# mainboard.net
KiCad netlist of a schematic drawn in EAGLE
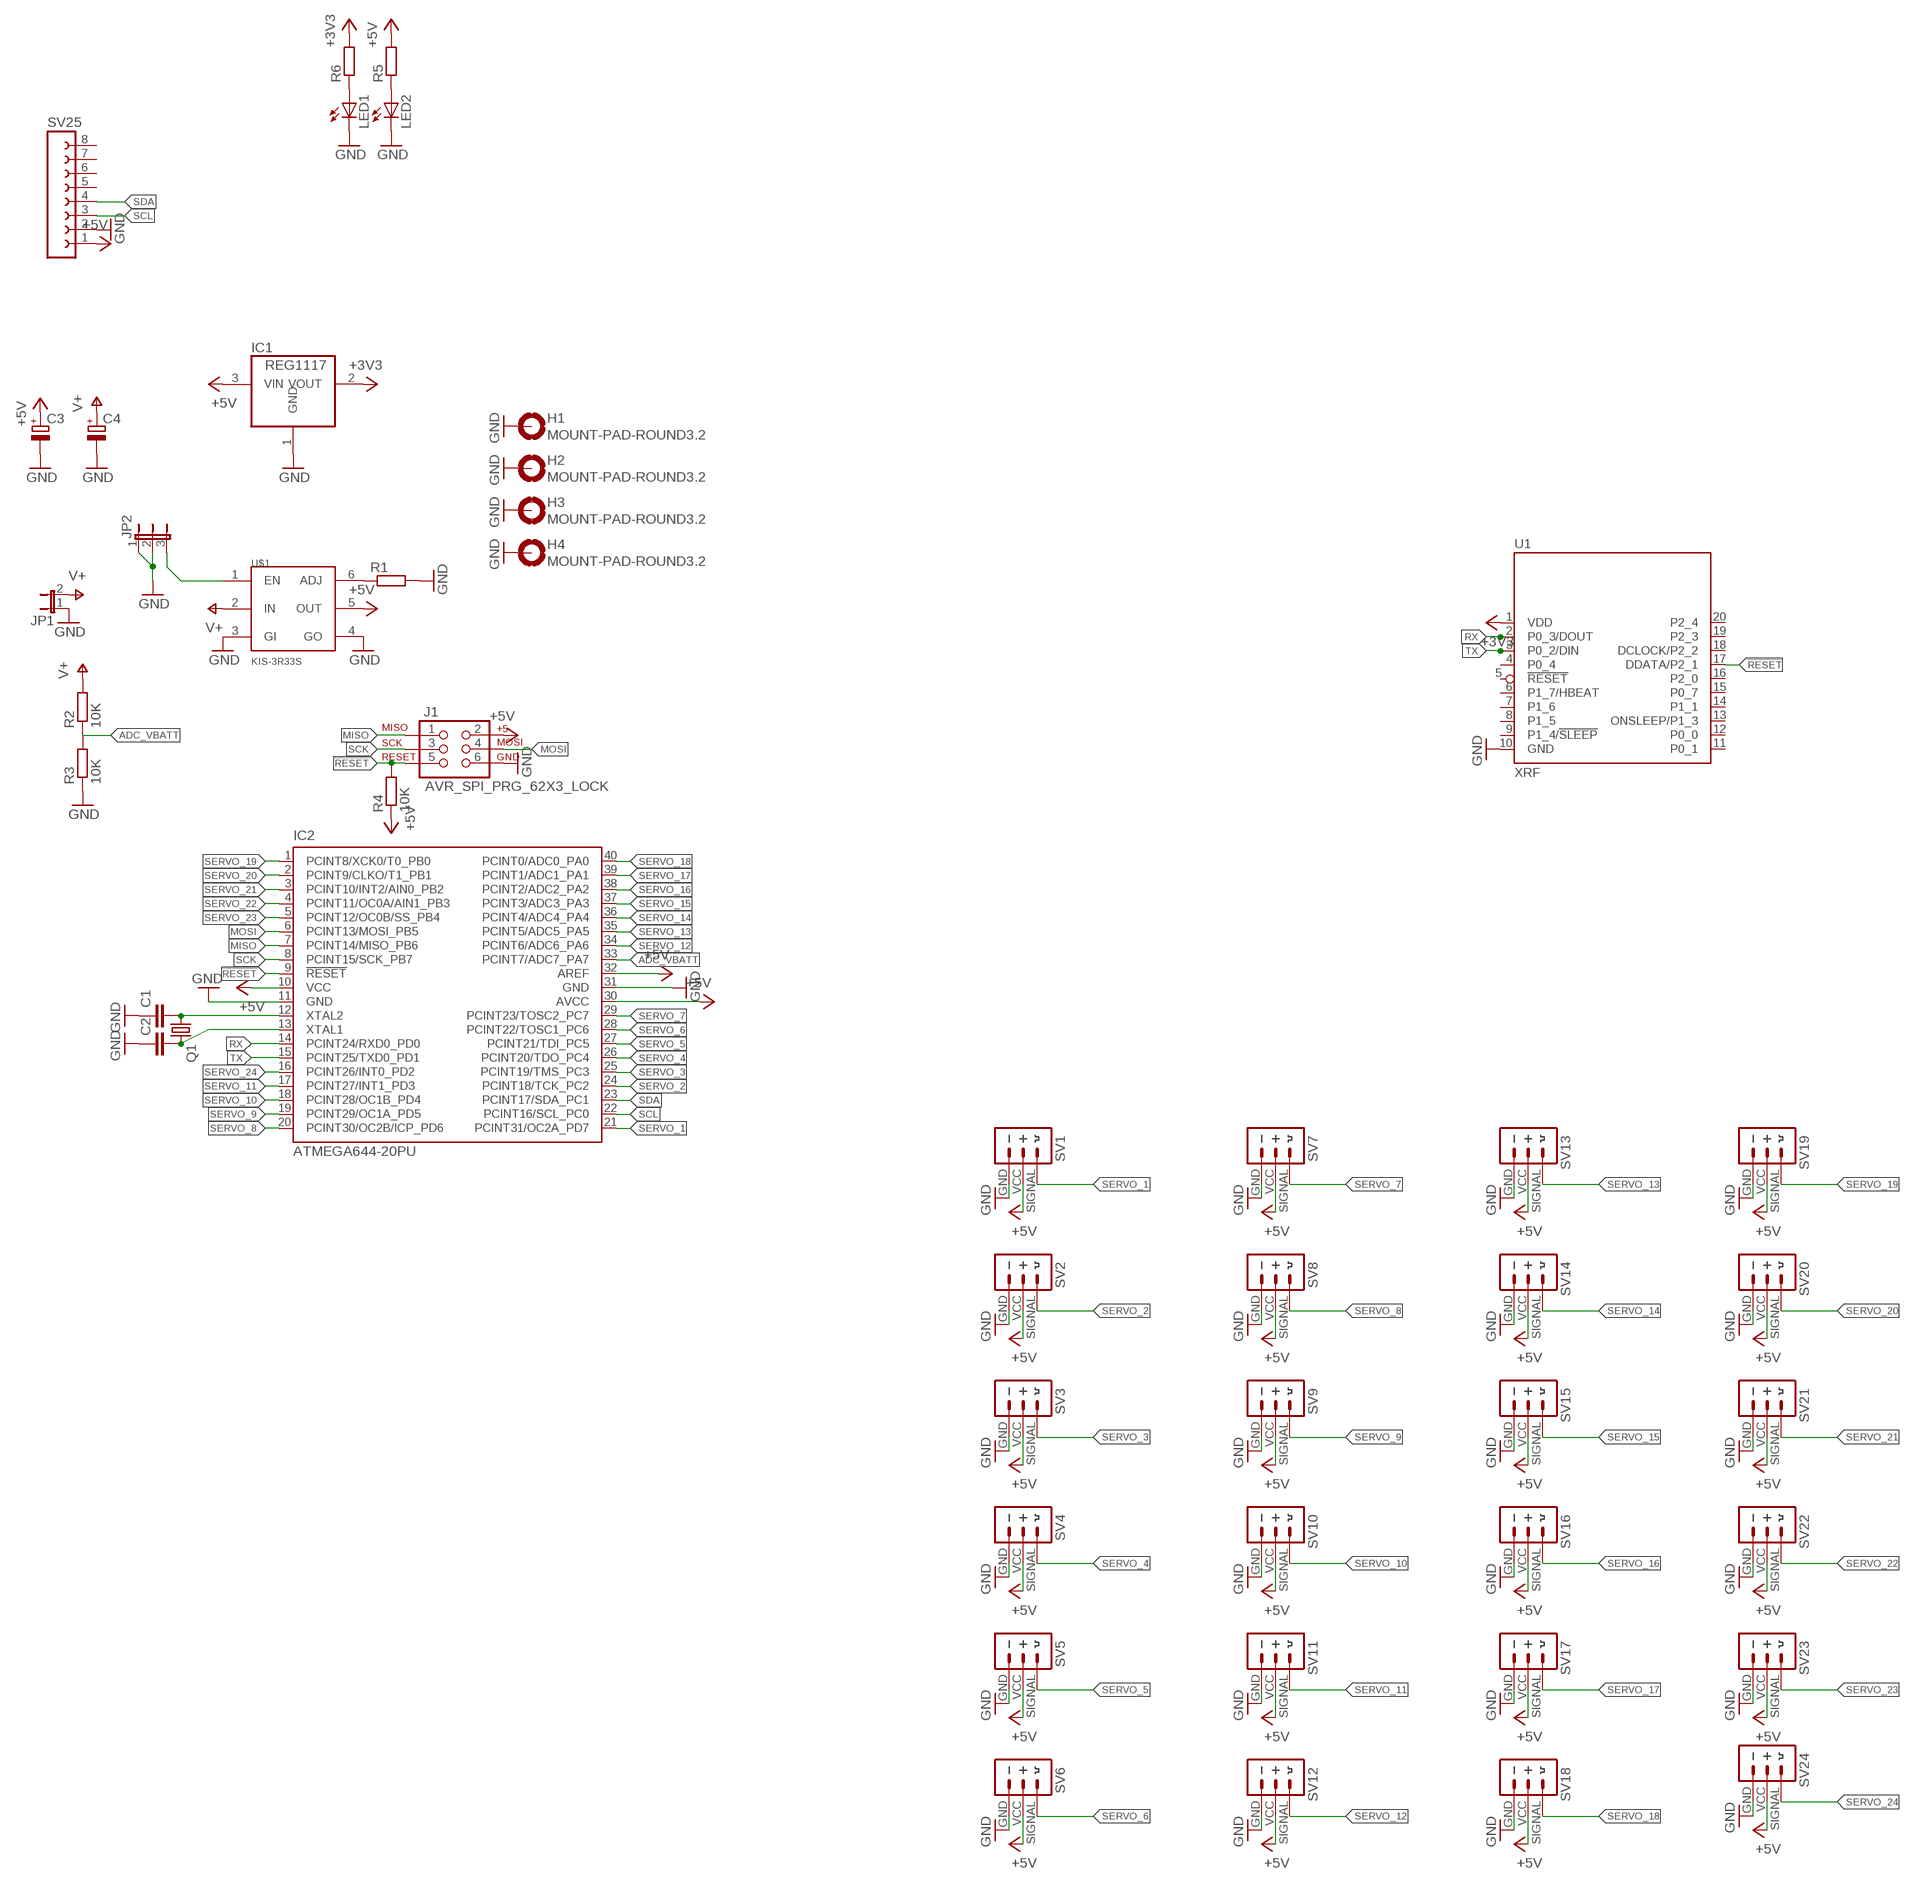
[diagram p0: schematic, sheet 1]

(export (version "E")
  (design (tool "Eeschema 10.0.6"))
  (components
    (comp (ref "C1")
      (value "C-EU025-025X050")
      (footprint "eagle-import:C025-025X050")
      (libsource (lib "eagle-import") (part "C-EU025-025X050"))
    )
    (comp (ref "C2")
      (value "C-EU025-025X050")
      (footprint "eagle-import:C025-025X050")
      (libsource (lib "eagle-import") (part "C-EU025-025X050"))
    )
    (comp (ref "C3")
      (value "CPOL-EUE2.5-7")
      (footprint "eagle-import:E2,5-7")
      (libsource (lib "eagle-import") (part "CPOL-EUE2.5-7"))
    )
    (comp (ref "C4")
      (value "CPOL-EUE2.5-7")
      (footprint "eagle-import:E2,5-7")
      (libsource (lib "eagle-import") (part "CPOL-EUE2.5-7"))
    )
    (comp (ref "H1")
      (value "MOUNT-PAD-ROUND3.2")
      (footprint "eagle-import:3,2-PAD")
      (libsource (lib "eagle-import") (part "MOUNT-PAD-ROUND3.2"))
    )
    (comp (ref "H2")
      (value "MOUNT-PAD-ROUND3.2")
      (footprint "eagle-import:3,2-PAD")
      (libsource (lib "eagle-import") (part "MOUNT-PAD-ROUND3.2"))
    )
    (comp (ref "H3")
      (value "MOUNT-PAD-ROUND3.2")
      (footprint "eagle-import:3,2-PAD")
      (libsource (lib "eagle-import") (part "MOUNT-PAD-ROUND3.2"))
    )
    (comp (ref "H4")
      (value "MOUNT-PAD-ROUND3.2")
      (footprint "eagle-import:3,2-PAD")
      (libsource (lib "eagle-import") (part "MOUNT-PAD-ROUND3.2"))
    )
    (comp (ref "IC1")
      (value "REG1117")
      (footprint "eagle-import:SOT223")
      (libsource (lib "eagle-import") (part "REG1117"))
    )
    (comp (ref "IC2")
      (value "ATMEGA644-20PU")
      (footprint "eagle-import:DIL40")
      (libsource (lib "eagle-import") (part "ATMEGA644-PU20"))
    )
    (comp (ref "J1")
      (value "AVR_SPI_PRG_62X3_LOCK")
      (footprint "eagle-import:2X3_LOCK")
      (libsource (lib "eagle-import") (part "AVR_SPI_PRG_62X3_LOCK"))
    )
    (comp (ref "JP1")
      (value "JP1E")
      (footprint "eagle-import:JP1")
      (libsource (lib "eagle-import") (part "JP1E"))
    )
    (comp (ref "JP2")
      (value "JP2E")
      (footprint "eagle-import:JP2")
      (libsource (lib "eagle-import") (part "JP2E"))
    )
    (comp (ref "LED1")
      (value "LED5MM")
      (footprint "eagle-import:LED5MM")
      (libsource (lib "eagle-import") (part "LED5MM"))
    )
    (comp (ref "LED2")
      (value "LED5MM")
      (footprint "eagle-import:LED5MM")
      (libsource (lib "eagle-import") (part "LED5MM"))
    )
    (comp (ref "Q1")
      (value "CRYSTALHC49U-V")
      (footprint "eagle-import:HC49U-V")
      (libsource (lib "eagle-import") (part "CRYSTALHC49U-V"))
    )
    (comp (ref "R1")
      (value "R-EU_0207/10")
      (footprint "eagle-import:0207_10")
      (libsource (lib "eagle-import") (part "R-EU_0207/10"))
    )
    (comp (ref "R2")
      (value "10K")
      (footprint "eagle-import:0204_5")
      (libsource (lib "eagle-import") (part "R-EU_0204/5"))
    )
    (comp (ref "R3")
      (value "10K")
      (footprint "eagle-import:0204_5")
      (libsource (lib "eagle-import") (part "R-EU_0204/5"))
    )
    (comp (ref "R4")
      (value "10K")
      (footprint "eagle-import:0204V")
      (libsource (lib "eagle-import") (part "R-EU_0204/2V"))
    )
    (comp (ref "R5")
      (value "R-EU_0204/2V")
      (footprint "eagle-import:0204V")
      (libsource (lib "eagle-import") (part "R-EU_0204/2V"))
    )
    (comp (ref "R6")
      (value "R-EU_0204/2V")
      (footprint "eagle-import:0204V")
      (libsource (lib "eagle-import") (part "R-EU_0204/2V"))
    )
    (comp (ref "SV1")
      (value "SERVO")
      (footprint "eagle-import:SERVO")
      (libsource (lib "eagle-import") (part "SERVO"))
    )
    (comp (ref "SV2")
      (value "SERVO")
      (footprint "eagle-import:SERVO")
      (libsource (lib "eagle-import") (part "SERVO"))
    )
    (comp (ref "SV3")
      (value "SERVO")
      (footprint "eagle-import:SERVO")
      (libsource (lib "eagle-import") (part "SERVO"))
    )
    (comp (ref "SV4")
      (value "SERVO")
      (footprint "eagle-import:SERVO")
      (libsource (lib "eagle-import") (part "SERVO"))
    )
    (comp (ref "SV5")
      (value "SERVO")
      (footprint "eagle-import:SERVO")
      (libsource (lib "eagle-import") (part "SERVO"))
    )
    (comp (ref "SV6")
      (value "SERVO")
      (footprint "eagle-import:SERVO")
      (libsource (lib "eagle-import") (part "SERVO"))
    )
    (comp (ref "SV7")
      (value "SERVO")
      (footprint "eagle-import:SERVO")
      (libsource (lib "eagle-import") (part "SERVO"))
    )
    (comp (ref "SV8")
      (value "SERVO")
      (footprint "eagle-import:SERVO")
      (libsource (lib "eagle-import") (part "SERVO"))
    )
    (comp (ref "SV9")
      (value "SERVO")
      (footprint "eagle-import:SERVO")
      (libsource (lib "eagle-import") (part "SERVO"))
    )
    (comp (ref "SV10")
      (value "SERVO")
      (footprint "eagle-import:SERVO")
      (libsource (lib "eagle-import") (part "SERVO"))
    )
    (comp (ref "SV11")
      (value "SERVO")
      (footprint "eagle-import:SERVO")
      (libsource (lib "eagle-import") (part "SERVO"))
    )
    (comp (ref "SV12")
      (value "SERVO")
      (footprint "eagle-import:SERVO")
      (libsource (lib "eagle-import") (part "SERVO"))
    )
    (comp (ref "SV13")
      (value "SERVO")
      (footprint "eagle-import:SERVO")
      (libsource (lib "eagle-import") (part "SERVO"))
    )
    (comp (ref "SV14")
      (value "SERVO")
      (footprint "eagle-import:SERVO")
      (libsource (lib "eagle-import") (part "SERVO"))
    )
    (comp (ref "SV15")
      (value "SERVO")
      (footprint "eagle-import:SERVO")
      (libsource (lib "eagle-import") (part "SERVO"))
    )
    (comp (ref "SV16")
      (value "SERVO")
      (footprint "eagle-import:SERVO")
      (libsource (lib "eagle-import") (part "SERVO"))
    )
    (comp (ref "SV17")
      (value "SERVO")
      (footprint "eagle-import:SERVO")
      (libsource (lib "eagle-import") (part "SERVO"))
    )
    (comp (ref "SV18")
      (value "SERVO")
      (footprint "eagle-import:SERVO")
      (libsource (lib "eagle-import") (part "SERVO"))
    )
    (comp (ref "SV19")
      (value "SERVO")
      (footprint "eagle-import:SERVO")
      (libsource (lib "eagle-import") (part "SERVO"))
    )
    (comp (ref "SV20")
      (value "SERVO")
      (footprint "eagle-import:SERVO")
      (libsource (lib "eagle-import") (part "SERVO"))
    )
    (comp (ref "SV21")
      (value "SERVO")
      (footprint "eagle-import:SERVO")
      (libsource (lib "eagle-import") (part "SERVO"))
    )
    (comp (ref "SV22")
      (value "SERVO")
      (footprint "eagle-import:SERVO")
      (libsource (lib "eagle-import") (part "SERVO"))
    )
    (comp (ref "SV23")
      (value "SERVO")
      (footprint "eagle-import:SERVO")
      (libsource (lib "eagle-import") (part "SERVO"))
    )
    (comp (ref "SV24")
      (value "SERVO")
      (footprint "eagle-import:SERVO")
      (libsource (lib "eagle-import") (part "SERVO"))
    )
    (comp (ref "SV25")
      (value "FE08-1")
      (footprint "eagle-import:FE08")
      (libsource (lib "eagle-import") (part "FE08-1"))
    )
    (comp (ref "U$1")
      (value "KIS-3R33S")
      (footprint "eagle-import:KIS-3R33S")
      (libsource (lib "eagle-import") (part "KIS-3R33S"))
    )
    (comp (ref "U1")
      (value "XRF")
      (footprint "eagle-import:XRF")
      (libsource (lib "eagle-import") (part "XRF"))
    )
  )
  (nets
    (net (code "1") (name "+3V3") (class "Default")
      (node (ref "IC1") (pin "2") (pinfunction "VOUT_2") (pintype "output"))
      (node (ref "R6") (pin "2") (pinfunction "2_2") (pintype "passive"))
      (node (ref "U1") (pin "1") (pinfunction "VDD_1") (pintype "power_in"))
    )
    (net (code "2") (name "+5V") (class "Default")
      (node (ref "C3") (pin "+") (pinfunction "+_+") (pintype "passive"))
      (node (ref "IC1") (pin "3") (pinfunction "VIN_3") (pintype "input"))
      (node (ref "IC2") (pin "10") (pinfunction "VCC_10") (pintype "power_in"))
      (node (ref "IC2") (pin "30") (pinfunction "AVCC_30") (pintype "power_in"))
      (node (ref "IC2") (pin "32") (pinfunction "AREF_32") (pintype "passive"))
      (node (ref "J1") (pin "2") (pinfunction "2_2") (pintype "passive"))
      (node (ref "R4") (pin "1") (pinfunction "1_1") (pintype "passive"))
      (node (ref "R5") (pin "2") (pinfunction "2_2") (pintype "passive"))
      (node (ref "SV1") (pin "VCC") (pinfunction "VCC_VCC") (pintype "passive"))
      (node (ref "SV10") (pin "VCC") (pinfunction "VCC_VCC") (pintype "passive"))
      (node (ref "SV11") (pin "VCC") (pinfunction "VCC_VCC") (pintype "passive"))
      (node (ref "SV12") (pin "VCC") (pinfunction "VCC_VCC") (pintype "passive"))
      (node (ref "SV13") (pin "VCC") (pinfunction "VCC_VCC") (pintype "passive"))
      (node (ref "SV14") (pin "VCC") (pinfunction "VCC_VCC") (pintype "passive"))
      (node (ref "SV15") (pin "VCC") (pinfunction "VCC_VCC") (pintype "passive"))
      (node (ref "SV16") (pin "VCC") (pinfunction "VCC_VCC") (pintype "passive"))
      (node (ref "SV17") (pin "VCC") (pinfunction "VCC_VCC") (pintype "passive"))
      (node (ref "SV18") (pin "VCC") (pinfunction "VCC_VCC") (pintype "passive"))
      (node (ref "SV19") (pin "VCC") (pinfunction "VCC_VCC") (pintype "passive"))
      (node (ref "SV2") (pin "VCC") (pinfunction "VCC_VCC") (pintype "passive"))
      (node (ref "SV20") (pin "VCC") (pinfunction "VCC_VCC") (pintype "passive"))
      (node (ref "SV21") (pin "VCC") (pinfunction "VCC_VCC") (pintype "passive"))
      (node (ref "SV22") (pin "VCC") (pinfunction "VCC_VCC") (pintype "passive"))
      (node (ref "SV23") (pin "VCC") (pinfunction "VCC_VCC") (pintype "passive"))
      (node (ref "SV24") (pin "VCC") (pinfunction "VCC_VCC") (pintype "passive"))
      (node (ref "SV25") (pin "1") (pinfunction "1_1") (pintype "passive"))
      (node (ref "SV3") (pin "VCC") (pinfunction "VCC_VCC") (pintype "passive"))
      (node (ref "SV4") (pin "VCC") (pinfunction "VCC_VCC") (pintype "passive"))
      (node (ref "SV5") (pin "VCC") (pinfunction "VCC_VCC") (pintype "passive"))
      (node (ref "SV6") (pin "VCC") (pinfunction "VCC_VCC") (pintype "passive"))
      (node (ref "SV7") (pin "VCC") (pinfunction "VCC_VCC") (pintype "passive"))
      (node (ref "SV8") (pin "VCC") (pinfunction "VCC_VCC") (pintype "passive"))
      (node (ref "SV9") (pin "VCC") (pinfunction "VCC_VCC") (pintype "passive"))
      (node (ref "U$1") (pin "5") (pinfunction "OUT_5") (pintype "bidirectional"))
    )
    (net (code "3") (name "/~{RESET}") (class "Default")
      (node (ref "IC2") (pin "9") (pinfunction "~{RESET}_9") (pintype "input"))
      (node (ref "J1") (pin "5") (pinfunction "5_5") (pintype "passive"))
      (node (ref "R4") (pin "2") (pinfunction "2_2") (pintype "passive"))
      (node (ref "U1") (pin "17") (pinfunction "DDATA/P2_1_17") (pintype "bidirectional"))
    )
    (net (code "4") (name "ADC_VBATT") (class "Default")
      (node (ref "IC2") (pin "33") (pinfunction "PCINT7/ADC7_PA7_33") (pintype "bidirectional"))
      (node (ref "R2") (pin "1") (pinfunction "1_1") (pintype "passive"))
      (node (ref "R3") (pin "2") (pinfunction "2_2") (pintype "passive"))
    )
    (net (code "5") (name "GND") (class "Default")
      (node (ref "C1") (pin "1") (pinfunction "1_1") (pintype "passive"))
      (node (ref "C2") (pin "1") (pinfunction "1_1") (pintype "passive"))
      (node (ref "C3") (pin "-") (pinfunction "-_-") (pintype "passive"))
      (node (ref "C4") (pin "-") (pinfunction "-_-") (pintype "passive"))
      (node (ref "H1") (pin "B3,2") (pinfunction "MOUNT_B3,2") (pintype "passive"))
      (node (ref "H2") (pin "B3,2") (pinfunction "MOUNT_B3,2") (pintype "passive"))
      (node (ref "H3") (pin "B3,2") (pinfunction "MOUNT_B3,2") (pintype "passive"))
      (node (ref "H4") (pin "B3,2") (pinfunction "MOUNT_B3,2") (pintype "passive"))
      (node (ref "IC1") (pin "1") (pinfunction "GND_1") (pintype "power_in"))
      (node (ref "IC2") (pin "11") (pinfunction "GND_11") (pintype "power_in"))
      (node (ref "IC2") (pin "31") (pinfunction "GND_31") (pintype "power_in"))
      (node (ref "J1") (pin "6") (pinfunction "6_6") (pintype "passive"))
      (node (ref "JP1") (pin "1") (pinfunction "1_1") (pintype "passive"))
      (node (ref "JP2") (pin "1") (pinfunction "1_1") (pintype "passive"))
      (node (ref "JP2") (pin "2") (pinfunction "2_2") (pintype "passive"))
      (node (ref "LED1") (pin "K") (pinfunction "C_K") (pintype "passive"))
      (node (ref "LED2") (pin "K") (pinfunction "C_K") (pintype "passive"))
      (node (ref "R1") (pin "2") (pinfunction "2_2") (pintype "passive"))
      (node (ref "R3") (pin "1") (pinfunction "1_1") (pintype "passive"))
      (node (ref "SV1") (pin "GND") (pinfunction "GND_GND") (pintype "passive"))
      (node (ref "SV10") (pin "GND") (pinfunction "GND_GND") (pintype "passive"))
      (node (ref "SV11") (pin "GND") (pinfunction "GND_GND") (pintype "passive"))
      (node (ref "SV12") (pin "GND") (pinfunction "GND_GND") (pintype "passive"))
      (node (ref "SV13") (pin "GND") (pinfunction "GND_GND") (pintype "passive"))
      (node (ref "SV14") (pin "GND") (pinfunction "GND_GND") (pintype "passive"))
      (node (ref "SV15") (pin "GND") (pinfunction "GND_GND") (pintype "passive"))
      (node (ref "SV16") (pin "GND") (pinfunction "GND_GND") (pintype "passive"))
      (node (ref "SV17") (pin "GND") (pinfunction "GND_GND") (pintype "passive"))
      (node (ref "SV18") (pin "GND") (pinfunction "GND_GND") (pintype "passive"))
      (node (ref "SV19") (pin "GND") (pinfunction "GND_GND") (pintype "passive"))
      (node (ref "SV2") (pin "GND") (pinfunction "GND_GND") (pintype "passive"))
      (node (ref "SV20") (pin "GND") (pinfunction "GND_GND") (pintype "passive"))
      (node (ref "SV21") (pin "GND") (pinfunction "GND_GND") (pintype "passive"))
      (node (ref "SV22") (pin "GND") (pinfunction "GND_GND") (pintype "passive"))
      (node (ref "SV23") (pin "GND") (pinfunction "GND_GND") (pintype "passive"))
      (node (ref "SV24") (pin "GND") (pinfunction "GND_GND") (pintype "passive"))
      (node (ref "SV25") (pin "2") (pinfunction "2_2") (pintype "passive"))
      (node (ref "SV3") (pin "GND") (pinfunction "GND_GND") (pintype "passive"))
      (node (ref "SV4") (pin "GND") (pinfunction "GND_GND") (pintype "passive"))
      (node (ref "SV5") (pin "GND") (pinfunction "GND_GND") (pintype "passive"))
      (node (ref "SV6") (pin "GND") (pinfunction "GND_GND") (pintype "passive"))
      (node (ref "SV7") (pin "GND") (pinfunction "GND_GND") (pintype "passive"))
      (node (ref "SV8") (pin "GND") (pinfunction "GND_GND") (pintype "passive"))
      (node (ref "SV9") (pin "GND") (pinfunction "GND_GND") (pintype "passive"))
      (node (ref "U$1") (pin "3") (pinfunction "GI_3") (pintype "power_in"))
      (node (ref "U$1") (pin "4") (pinfunction "GO_4") (pintype "power_in"))
      (node (ref "U1") (pin "10") (pinfunction "GND_10") (pintype "power_in"))
    )
    (net (code "6") (name "MISO") (class "Default")
      (node (ref "IC2") (pin "7") (pinfunction "PCINT14/MISO_PB6_7") (pintype "bidirectional"))
      (node (ref "J1") (pin "1") (pinfunction "1_1") (pintype "passive"))
    )
    (net (code "7") (name "MOSI") (class "Default")
      (node (ref "IC2") (pin "6") (pinfunction "PCINT13/MOSI_PB5_6") (pintype "bidirectional"))
      (node (ref "J1") (pin "4") (pinfunction "4_4") (pintype "passive"))
    )
    (net (code "8") (name "Net-(IC2-XTAL1)") (class "Default")
      (node (ref "C2") (pin "2") (pinfunction "2_2") (pintype "passive"))
      (node (ref "IC2") (pin "13") (pinfunction "XTAL1_13") (pintype "input"))
      (node (ref "Q1") (pin "2") (pinfunction "2_2") (pintype "passive"))
    )
    (net (code "9") (name "Net-(IC2-XTAL2)") (class "Default")
      (node (ref "C1") (pin "2") (pinfunction "2_2") (pintype "passive"))
      (node (ref "IC2") (pin "12") (pinfunction "XTAL2_12") (pintype "output"))
      (node (ref "Q1") (pin "1") (pinfunction "1_1") (pintype "passive"))
    )
    (net (code "10") (name "Net-(LED1-PadA)") (class "Default")
      (node (ref "LED1") (pin "A") (pinfunction "A_A") (pintype "passive"))
      (node (ref "R6") (pin "1") (pinfunction "1_1") (pintype "passive"))
    )
    (net (code "11") (name "Net-(LED2-PadA)") (class "Default")
      (node (ref "LED2") (pin "A") (pinfunction "A_A") (pintype "passive"))
      (node (ref "R5") (pin "1") (pinfunction "1_1") (pintype "passive"))
    )
    (net (code "12") (name "Net-(U$1-ADJ)") (class "Default")
      (node (ref "R1") (pin "1") (pinfunction "1_1") (pintype "passive"))
      (node (ref "U$1") (pin "6") (pinfunction "ADJ_6") (pintype "bidirectional"))
    )
    (net (code "13") (name "Net-(U$1-EN)") (class "Default")
      (node (ref "JP2") (pin "3") (pinfunction "3_3") (pintype "passive"))
      (node (ref "U$1") (pin "1") (pinfunction "EN_1") (pintype "bidirectional"))
    )
    (net (code "14") (name "RX") (class "Default")
      (node (ref "IC2") (pin "14") (pinfunction "PCINT24/RXD0_PD0_14") (pintype "bidirectional"))
      (node (ref "U1") (pin "2") (pinfunction "P0_3/DOUT_2") (pintype "output"))
    )
    (net (code "15") (name "SCK") (class "Default")
      (node (ref "IC2") (pin "8") (pinfunction "PCINT15/SCK_PB7_8") (pintype "bidirectional"))
      (node (ref "J1") (pin "3") (pinfunction "3_3") (pintype "passive"))
    )
    (net (code "16") (name "SCL") (class "Default")
      (node (ref "IC2") (pin "22") (pinfunction "PCINT16/SCL_PC0_22") (pintype "bidirectional"))
      (node (ref "SV25") (pin "3") (pinfunction "3_3") (pintype "passive"))
    )
    (net (code "17") (name "SDA") (class "Default")
      (node (ref "IC2") (pin "23") (pinfunction "PCINT17/SDA_PC1_23") (pintype "bidirectional"))
      (node (ref "SV25") (pin "4") (pinfunction "4_4") (pintype "passive"))
    )
    (net (code "18") (name "SERVO_1") (class "Default")
      (node (ref "IC2") (pin "21") (pinfunction "PCINT31/OC2A_PD7_21") (pintype "bidirectional"))
      (node (ref "SV1") (pin "SIGNAL") (pinfunction "SIGNAL_SIGNAL") (pintype "passive"))
    )
    (net (code "19") (name "SERVO_2") (class "Default")
      (node (ref "IC2") (pin "24") (pinfunction "PCINT18/TCK_PC2_24") (pintype "bidirectional"))
      (node (ref "SV2") (pin "SIGNAL") (pinfunction "SIGNAL_SIGNAL") (pintype "passive"))
    )
    (net (code "20") (name "SERVO_3") (class "Default")
      (node (ref "IC2") (pin "25") (pinfunction "PCINT19/TMS_PC3_25") (pintype "bidirectional"))
      (node (ref "SV3") (pin "SIGNAL") (pinfunction "SIGNAL_SIGNAL") (pintype "passive"))
    )
    (net (code "21") (name "SERVO_4") (class "Default")
      (node (ref "IC2") (pin "26") (pinfunction "PCINT20/TDO_PC4_26") (pintype "bidirectional"))
      (node (ref "SV4") (pin "SIGNAL") (pinfunction "SIGNAL_SIGNAL") (pintype "passive"))
    )
    (net (code "22") (name "SERVO_5") (class "Default")
      (node (ref "IC2") (pin "27") (pinfunction "PCINT21/TDI_PC5_27") (pintype "bidirectional"))
      (node (ref "SV5") (pin "SIGNAL") (pinfunction "SIGNAL_SIGNAL") (pintype "passive"))
    )
    (net (code "23") (name "SERVO_6") (class "Default")
      (node (ref "IC2") (pin "28") (pinfunction "PCINT22/TOSC1_PC6_28") (pintype "bidirectional"))
      (node (ref "SV6") (pin "SIGNAL") (pinfunction "SIGNAL_SIGNAL") (pintype "passive"))
    )
    (net (code "24") (name "SERVO_7") (class "Default")
      (node (ref "IC2") (pin "29") (pinfunction "PCINT23/TOSC2_PC7_29") (pintype "bidirectional"))
      (node (ref "SV7") (pin "SIGNAL") (pinfunction "SIGNAL_SIGNAL") (pintype "passive"))
    )
    (net (code "25") (name "SERVO_8") (class "Default")
      (node (ref "IC2") (pin "20") (pinfunction "PCINT30/OC2B/ICP_PD6_20") (pintype "bidirectional"))
      (node (ref "SV8") (pin "SIGNAL") (pinfunction "SIGNAL_SIGNAL") (pintype "passive"))
    )
    (net (code "26") (name "SERVO_9") (class "Default")
      (node (ref "IC2") (pin "19") (pinfunction "PCINT29/OC1A_PD5_19") (pintype "bidirectional"))
      (node (ref "SV9") (pin "SIGNAL") (pinfunction "SIGNAL_SIGNAL") (pintype "passive"))
    )
    (net (code "27") (name "SERVO_10") (class "Default")
      (node (ref "IC2") (pin "18") (pinfunction "PCINT28/OC1B_PD4_18") (pintype "bidirectional"))
      (node (ref "SV10") (pin "SIGNAL") (pinfunction "SIGNAL_SIGNAL") (pintype "passive"))
    )
    (net (code "28") (name "SERVO_11") (class "Default")
      (node (ref "IC2") (pin "17") (pinfunction "PCINT27/INT1_PD3_17") (pintype "bidirectional"))
      (node (ref "SV11") (pin "SIGNAL") (pinfunction "SIGNAL_SIGNAL") (pintype "passive"))
    )
    (net (code "29") (name "SERVO_12") (class "Default")
      (node (ref "IC2") (pin "34") (pinfunction "PCINT6/ADC6_PA6_34") (pintype "bidirectional"))
      (node (ref "SV12") (pin "SIGNAL") (pinfunction "SIGNAL_SIGNAL") (pintype "passive"))
    )
    (net (code "30") (name "SERVO_13") (class "Default")
      (node (ref "IC2") (pin "35") (pinfunction "PCINT5/ADC5_PA5_35") (pintype "bidirectional"))
      (node (ref "SV13") (pin "SIGNAL") (pinfunction "SIGNAL_SIGNAL") (pintype "passive"))
    )
    (net (code "31") (name "SERVO_14") (class "Default")
      (node (ref "IC2") (pin "36") (pinfunction "PCINT4/ADC4_PA4_36") (pintype "bidirectional"))
      (node (ref "SV14") (pin "SIGNAL") (pinfunction "SIGNAL_SIGNAL") (pintype "passive"))
    )
    (net (code "32") (name "SERVO_15") (class "Default")
      (node (ref "IC2") (pin "37") (pinfunction "PCINT3/ADC3_PA3_37") (pintype "bidirectional"))
      (node (ref "SV15") (pin "SIGNAL") (pinfunction "SIGNAL_SIGNAL") (pintype "passive"))
    )
    (net (code "33") (name "SERVO_16") (class "Default")
      (node (ref "IC2") (pin "38") (pinfunction "PCINT2/ADC2_PA2_38") (pintype "bidirectional"))
      (node (ref "SV16") (pin "SIGNAL") (pinfunction "SIGNAL_SIGNAL") (pintype "passive"))
    )
    (net (code "34") (name "SERVO_17") (class "Default")
      (node (ref "IC2") (pin "39") (pinfunction "PCINT1/ADC1_PA1_39") (pintype "bidirectional"))
      (node (ref "SV17") (pin "SIGNAL") (pinfunction "SIGNAL_SIGNAL") (pintype "passive"))
    )
    (net (code "35") (name "SERVO_18") (class "Default")
      (node (ref "IC2") (pin "40") (pinfunction "PCINT0/ADC0_PA0_40") (pintype "bidirectional"))
      (node (ref "SV18") (pin "SIGNAL") (pinfunction "SIGNAL_SIGNAL") (pintype "passive"))
    )
    (net (code "36") (name "SERVO_19") (class "Default")
      (node (ref "IC2") (pin "1") (pinfunction "PCINT8/XCK0/T0_PB0_1") (pintype "bidirectional"))
      (node (ref "SV19") (pin "SIGNAL") (pinfunction "SIGNAL_SIGNAL") (pintype "passive"))
    )
    (net (code "37") (name "SERVO_20") (class "Default")
      (node (ref "IC2") (pin "2") (pinfunction "PCINT9/CLKO/T1_PB1_2") (pintype "bidirectional"))
      (node (ref "SV20") (pin "SIGNAL") (pinfunction "SIGNAL_SIGNAL") (pintype "passive"))
    )
    (net (code "38") (name "SERVO_21") (class "Default")
      (node (ref "IC2") (pin "3") (pinfunction "PCINT10/INT2/AIN0_PB2_3") (pintype "bidirectional"))
      (node (ref "SV21") (pin "SIGNAL") (pinfunction "SIGNAL_SIGNAL") (pintype "passive"))
    )
    (net (code "39") (name "SERVO_22") (class "Default")
      (node (ref "IC2") (pin "4") (pinfunction "PCINT11/OC0A/AIN1_PB3_4") (pintype "bidirectional"))
      (node (ref "SV22") (pin "SIGNAL") (pinfunction "SIGNAL_SIGNAL") (pintype "passive"))
    )
    (net (code "40") (name "SERVO_23") (class "Default")
      (node (ref "IC2") (pin "5") (pinfunction "PCINT12/OC0B/SS_PB4_5") (pintype "bidirectional"))
      (node (ref "SV23") (pin "SIGNAL") (pinfunction "SIGNAL_SIGNAL") (pintype "passive"))
    )
    (net (code "41") (name "SERVO_24") (class "Default")
      (node (ref "IC2") (pin "16") (pinfunction "PCINT26/INT0_PD2_16") (pintype "bidirectional"))
      (node (ref "SV24") (pin "SIGNAL") (pinfunction "SIGNAL_SIGNAL") (pintype "passive"))
    )
    (net (code "42") (name "TX") (class "Default")
      (node (ref "IC2") (pin "15") (pinfunction "PCINT25/TXD0_PD1_15") (pintype "bidirectional"))
      (node (ref "U1") (pin "3") (pinfunction "P0_2/DIN_3") (pintype "input"))
    )
    (net (code "43") (name "V+") (class "Default")
      (node (ref "C4") (pin "+") (pinfunction "+_+") (pintype "passive"))
      (node (ref "JP1") (pin "2") (pinfunction "2_2") (pintype "passive"))
      (node (ref "R2") (pin "2") (pinfunction "2_2") (pintype "passive"))
      (node (ref "U$1") (pin "2") (pinfunction "IN_2") (pintype "bidirectional"))
    )
    (net (code "44") (name "unconnected-(SV25-Pad5)") (class "Default")
      (node (ref "SV25") (pin "5") (pinfunction "5_5") (pintype "passive"))
    )
    (net (code "45") (name "unconnected-(SV25-Pad6)") (class "Default")
      (node (ref "SV25") (pin "6") (pinfunction "6_6") (pintype "passive"))
    )
    (net (code "46") (name "unconnected-(SV25-Pad7)") (class "Default")
      (node (ref "SV25") (pin "7") (pinfunction "7_7") (pintype "passive"))
    )
    (net (code "47") (name "unconnected-(SV25-Pad8)") (class "Default")
      (node (ref "SV25") (pin "8") (pinfunction "8_8") (pintype "passive"))
    )
    (net (code "48") (name "unconnected-(U1-DCLOCK{slash}P2_2-Pad18)") (class "Default")
      (node (ref "U1") (pin "18") (pinfunction "DCLOCK/P2_2_18") (pintype "bidirectional"))
    )
    (net (code "49") (name "unconnected-(U1-ONSLEEP{slash}P1_3-Pad13)") (class "Default")
      (node (ref "U1") (pin "13") (pinfunction "ONSLEEP/P1_3_13") (pintype "bidirectional"))
    )
    (net (code "50") (name "unconnected-(U1-P0_0-Pad12)") (class "Default")
      (node (ref "U1") (pin "12") (pinfunction "P0_0_12") (pintype "bidirectional"))
    )
    (net (code "51") (name "unconnected-(U1-P0_1-Pad11)") (class "Default")
      (node (ref "U1") (pin "11") (pinfunction "P0_1_11") (pintype "bidirectional"))
    )
    (net (code "52") (name "unconnected-(U1-P0_4-Pad4)") (class "Default")
      (node (ref "U1") (pin "4") (pinfunction "P0_4_4") (pintype "bidirectional"))
    )
    (net (code "53") (name "unconnected-(U1-P0_7-Pad15)") (class "Default")
      (node (ref "U1") (pin "15") (pinfunction "P0_7_15") (pintype "bidirectional"))
    )
    (net (code "54") (name "unconnected-(U1-P1_1-Pad14)") (class "Default")
      (node (ref "U1") (pin "14") (pinfunction "P1_1_14") (pintype "bidirectional"))
    )
    (net (code "55") (name "unconnected-(U1-P1_4{slash}~{SLEEP}-Pad9)") (class "Default")
      (node (ref "U1") (pin "9") (pinfunction "P1_4/~{SLEEP}_9") (pintype "bidirectional"))
    )
    (net (code "56") (name "unconnected-(U1-P1_5-Pad8)") (class "Default")
      (node (ref "U1") (pin "8") (pinfunction "P1_5_8") (pintype "bidirectional"))
    )
    (net (code "57") (name "unconnected-(U1-P1_6-Pad7)") (class "Default")
      (node (ref "U1") (pin "7") (pinfunction "P1_6_7") (pintype "bidirectional"))
    )
    (net (code "58") (name "unconnected-(U1-P1_7{slash}HBEAT-Pad6)") (class "Default")
      (node (ref "U1") (pin "6") (pinfunction "P1_7/HBEAT_6") (pintype "bidirectional"))
    )
    (net (code "59") (name "unconnected-(U1-P2_0-Pad16)") (class "Default")
      (node (ref "U1") (pin "16") (pinfunction "P2_0_16") (pintype "input"))
    )
    (net (code "60") (name "unconnected-(U1-P2_3-Pad19)") (class "Default")
      (node (ref "U1") (pin "19") (pinfunction "P2_3_19") (pintype "bidirectional"))
    )
    (net (code "61") (name "unconnected-(U1-P2_4-Pad20)") (class "Default")
      (node (ref "U1") (pin "20") (pinfunction "P2_4_20") (pintype "bidirectional"))
    )
    (net (code "62") (name "unconnected-(U1-~{RESET}-Pad5)") (class "Default")
      (node (ref "U1") (pin "5") (pinfunction "~{RESET}_5") (pintype "input"))
    )
  )
)
